# pure_battery.net
KiCad netlist of a schematic drawn in EAGLE
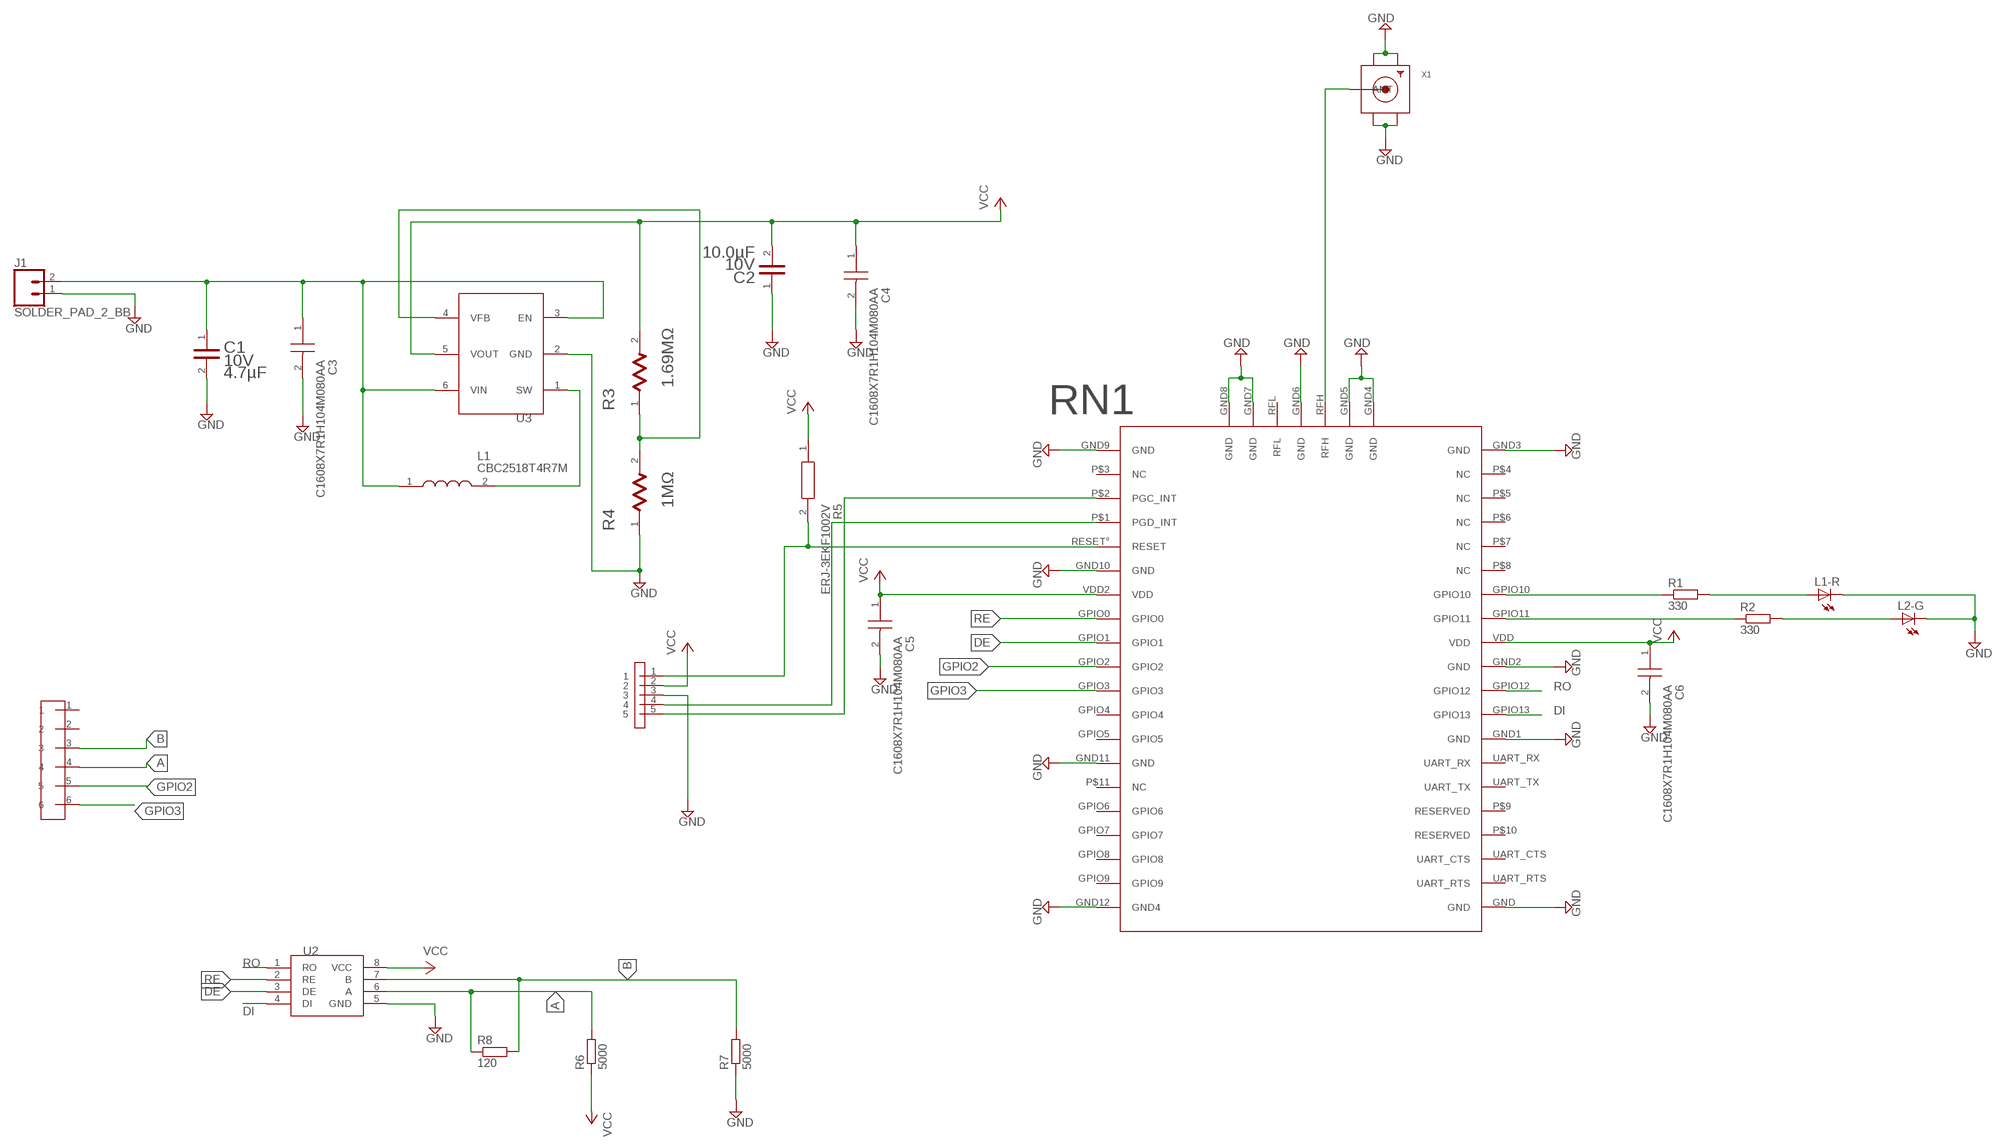
[diagram p0: schematic, sheet 1]

(export (version "E")
  (design (tool "Eeschema 10.0.6"))
  (components
    (comp (ref "C1")
      (value "KEMET_C0603C475K8PACTUKEMET_C0603C475K8PACTU_0_0")
      (footprint "eagle-import:KEMET_C0603C475K8PACTU_0")
      (fields
        (field (name "DIGIKEY_PART_NUMBER") "399-5503-1-ND")
        (field (name "MF") "Kemet")
        (field (name "MOUSER_PART_NUMBER") "80-C0603C475K8P")
      )
      (libsource (lib "eagle-import") (part "KEMET_C0603C475K8PACTUKEMET_C0603C475K8PACTU_0_0"))
    )
    (comp (ref "C2")
      (value "TDK_C1608X5R1A106M080ACTDK_C1608X5R1A106M080AC_0_0")
      (footprint "eagle-import:TDK_C1608X5R1A106M080AC_0")
      (fields
        (field (name "DIGIKEY_PART_NUMBER") "445-6853-1-ND")
        (field (name "MF") "TDK")
        (field (name "MOUSER_PART_NUMBER") "810-C1608X5R1A106M")
      )
      (libsource (lib "eagle-import") (part "TDK_C1608X5R1A106M080ACTDK_C1608X5R1A106M080AC_0_0"))
    )
    (comp (ref "C3")
      (value "C1608X7R1H104M080AA")
      (footprint "eagle-import:CAPC1608X80N")
      (fields (field (name "MOUSER_PART_NUMBER") "810-C1608X7R1H104M"))
      (libsource (lib "eagle-import") (part "C1608X7R1H104M080AA"))
    )
    (comp (ref "C4")
      (value "C1608X7R1H104M080AA")
      (footprint "eagle-import:CAPC1608X80N")
      (fields (field (name "MOUSER_PART_NUMBER") "810-C1608X7R1H104M"))
      (libsource (lib "eagle-import") (part "C1608X7R1H104M080AA"))
    )
    (comp (ref "C5")
      (value "C1608X7R1H104M080AA")
      (footprint "eagle-import:CAPC1608X80N")
      (fields (field (name "MOUSER_PART_NUMBER") "810-C1608X7R1H104M"))
      (libsource (lib "eagle-import") (part "C1608X7R1H104M080AA"))
    )
    (comp (ref "C6")
      (value "C1608X7R1H104M080AA")
      (footprint "eagle-import:CAPC1608X80N")
      (fields (field (name "MOUSER_PART_NUMBER") "810-C1608X7R1H104M"))
      (libsource (lib "eagle-import") (part "C1608X7R1H104M080AA"))
    )
    (comp (ref "J1")
      (value "SOLDER_PAD_2_BB")
      (footprint "eagle-import:SOLDER_PAD_2")
      (libsource (lib "eagle-import") (part "SOLDER_PAD_2_BB"))
    )
    (comp (ref "L1")
      (value "CBC2518T4R7M")
      (footprint "eagle-import:INDC2518X200N")
      (fields (field (name "MOUSER_PART_NUMBER") "963-CBC2518T4R7M"))
      (libsource (lib "eagle-import") (part "CBC2518T4R7M"))
    )
    (comp (ref "L1-R")
      (value "LEDCHIP-LED0603")
      (footprint "eagle-import:CHIP-LED0603")
      (libsource (lib "eagle-import") (part "LEDCHIP-LED0603"))
    )
    (comp (ref "L2-G")
      (value "LEDCHIP-LED0603")
      (footprint "eagle-import:CHIP-LED0603")
      (libsource (lib "eagle-import") (part "LEDCHIP-LED0603"))
    )
    (comp (ref "R1")
      (value "330")
      (footprint "eagle-import:R0603")
      (libsource (lib "eagle-import") (part "R-EU_R0603"))
    )
    (comp (ref "R2")
      (value "330")
      (footprint "eagle-import:R0603")
      (libsource (lib "eagle-import") (part "R-EU_R0603"))
    )
    (comp (ref "R3")
      (value "VISHAY_CRCW06031M69FKEAVISHAY_CRCW06031M69FKEA_0_1")
      (footprint "eagle-import:VISHAY_CRCW06031M69FKEA_1")
      (fields
        (field (name "APPROVED_ALTERNATE_PART_NUMBER") "541-1.00HHCT-ND")
        (field (name "DIGIKEY_PART_NUMBER") "541-1.69MHTR-ND")
        (field (name "MF") "Vishay")
      )
      (libsource (lib "eagle-import") (part "VISHAY_CRCW06031M69FKEAVISHAY_CRCW06031M69FKEA_0_1"))
    )
    (comp (ref "R4")
      (value "STACKPOLE_RMCF0603FT1M00STACKPOLE_RMCF0603FT1M00_0_1")
      (footprint "eagle-import:STACKPOLE_RMCF0603FT1M00_1")
      (fields
        (field (name "APPROVED_ALTERNATE_PART_NUMBER") "541-1.00HHCT-ND")
        (field (name "DIGIKEY_PART_NUMBER") "RMCF0603FT1M00-ND")
        (field (name "MF") "Stackpole")
      )
      (libsource (lib "eagle-import") (part "STACKPOLE_RMCF0603FT1M00STACKPOLE_RMCF0603FT1M00_0_1"))
    )
    (comp (ref "R5")
      (value "ERJ-3EKF1002V")
      (footprint "eagle-import:RESC1608X55N")
      (fields (field (name "MOUSER_PART_NUMBER") "667-ERJ-3EKF1002V"))
      (libsource (lib "eagle-import") (part "ERJ-3EKF1002V"))
    )
    (comp (ref "R6")
      (value "5000")
      (footprint "eagle-import:R0805")
      (libsource (lib "eagle-import") (part "R-EU_R0805"))
    )
    (comp (ref "R7")
      (value "5000")
      (footprint "eagle-import:R0805")
      (libsource (lib "eagle-import") (part "R-EU_R0805"))
    )
    (comp (ref "R8")
      (value "120")
      (footprint "eagle-import:R0805")
      (libsource (lib "eagle-import") (part "R-EU_R0805"))
    )
    (comp (ref "RN1")
      (value "NEW_RN2483")
      (footprint "eagle-import:NEW_RN2483")
      (libsource (lib "eagle-import") (part "NEW_RN2483"))
    )
    (comp (ref "U$1")
      (value "CONNECTOR6_V2")
      (footprint "eagle-import:CONNECTOR6_V2")
      (libsource (lib "eagle-import") (part "CONNECTOR6_V2"))
    )
    (comp (ref "U$2")
      (value "ICSP_V2")
      (footprint "eagle-import:ICSP_V2")
      (libsource (lib "eagle-import") (part "ICSP_V2"))
    )
    (comp (ref "U2")
      (value "AMD3485E")
      (footprint "eagle-import:AMD3485E")
      (libsource (lib "eagle-import") (part "AMD3485E"))
    )
    (comp (ref "U3")
      (value "MCP16252")
      (footprint "eagle-import:MCP16252")
      (libsource (lib "eagle-import") (part "MCP16252"))
    )
    (comp (ref "X1")
      (value "SMACONNECTOR_EDGE")
      (footprint "eagle-import:SMA_EDGELAUNCH")
      (libsource (lib "eagle-import") (part "SMACONNECTOR_EDGE"))
    )
  )
  (nets
    (net (code "1") (name "/DI") (class "Default")
      (node (ref "RN1") (pin "GPIO13") (pinfunction "GPIO13_GPIO13") (pintype "bidirectional"))
      (node (ref "U2") (pin "4") (pinfunction "DI_4") (pintype "bidirectional"))
    )
    (net (code "2") (name "/RO") (class "Default")
      (node (ref "RN1") (pin "GPIO12") (pinfunction "GPIO12_GPIO12") (pintype "bidirectional"))
      (node (ref "U2") (pin "1") (pinfunction "RO_1") (pintype "bidirectional"))
    )
    (net (code "3") (name "A") (class "Default")
      (node (ref "R6") (pin "2") (pinfunction "2_2") (pintype "passive"))
      (node (ref "R8") (pin "1") (pinfunction "1_1") (pintype "passive"))
      (node (ref "U$1") (pin "4") (pinfunction "4_4") (pintype "bidirectional"))
      (node (ref "U2") (pin "6") (pinfunction "A_6") (pintype "bidirectional"))
    )
    (net (code "4") (name "B") (class "Default")
      (node (ref "R7") (pin "2") (pinfunction "2_2") (pintype "passive"))
      (node (ref "R8") (pin "2") (pinfunction "2_2") (pintype "passive"))
      (node (ref "U$1") (pin "3") (pinfunction "3_3") (pintype "bidirectional"))
      (node (ref "U2") (pin "7") (pinfunction "B_7") (pintype "bidirectional"))
    )
    (net (code "5") (name "DE") (class "Default")
      (node (ref "RN1") (pin "GPIO1") (pinfunction "GPIO1_GPIO1") (pintype "bidirectional"))
      (node (ref "U2") (pin "3") (pinfunction "DE_3") (pintype "bidirectional"))
    )
    (net (code "6") (name "GND") (class "Default")
      (node (ref "C1") (pin "2") (pinfunction "2_2") (pintype "bidirectional"))
      (node (ref "C2") (pin "1") (pinfunction "1_1") (pintype "bidirectional"))
      (node (ref "C3") (pin "2") (pinfunction "2_2") (pintype "bidirectional"))
      (node (ref "C4") (pin "2") (pinfunction "2_2") (pintype "bidirectional"))
      (node (ref "C5") (pin "2") (pinfunction "2_2") (pintype "bidirectional"))
      (node (ref "C6") (pin "2") (pinfunction "2_2") (pintype "bidirectional"))
      (node (ref "J1") (pin "1") (pinfunction "1_1") (pintype "passive"))
      (node (ref "L1-R") (pin "C") (pinfunction "C_C") (pintype "passive"))
      (node (ref "L2-G") (pin "C") (pinfunction "C_C") (pintype "passive"))
      (node (ref "R4") (pin "1") (pinfunction "1_1") (pintype "passive"))
      (node (ref "R7") (pin "1") (pinfunction "1_1") (pintype "passive"))
      (node (ref "RN1") (pin "GND") (pinfunction "GND_GND") (pintype "bidirectional"))
      (node (ref "RN1") (pin "GND1") (pinfunction "GND_GND1") (pintype "bidirectional"))
      (node (ref "RN1") (pin "GND10") (pinfunction "GND_GND10") (pintype "bidirectional"))
      (node (ref "RN1") (pin "GND11") (pinfunction "GND_GND11") (pintype "bidirectional"))
      (node (ref "RN1") (pin "GND12") (pinfunction "GND4_GND12") (pintype "bidirectional"))
      (node (ref "RN1") (pin "GND2") (pinfunction "GND_GND2") (pintype "bidirectional"))
      (node (ref "RN1") (pin "GND3") (pinfunction "GND_GND3") (pintype "bidirectional"))
      (node (ref "RN1") (pin "GND4") (pinfunction "GND_GND4") (pintype "bidirectional"))
      (node (ref "RN1") (pin "GND5") (pinfunction "GND_GND5") (pintype "bidirectional"))
      (node (ref "RN1") (pin "GND6") (pinfunction "GND_GND6") (pintype "bidirectional"))
      (node (ref "RN1") (pin "GND7") (pinfunction "GND_GND7") (pintype "bidirectional"))
      (node (ref "RN1") (pin "GND8") (pinfunction "GND_GND8") (pintype "bidirectional"))
      (node (ref "RN1") (pin "GND9") (pinfunction "GND_GND9") (pintype "bidirectional"))
      (node (ref "U$2") (pin "3") (pinfunction "3_3") (pintype "bidirectional"))
      (node (ref "U2") (pin "5") (pinfunction "GND_5") (pintype "bidirectional"))
      (node (ref "U3") (pin "2") (pinfunction "GND_2") (pintype "bidirectional"))
      (node (ref "X1") (pin "GND@1") (pinfunction "GND4_GND@1") (pintype "power_in"))
      (node (ref "X1") (pin "GND@2") (pinfunction "GND3_GND@2") (pintype "power_in"))
      (node (ref "X1") (pin "GND@3") (pinfunction "GND2_GND@3") (pintype "power_in"))
      (node (ref "X1") (pin "GND@4") (pinfunction "GND1_GND@4") (pintype "power_in"))
    )
    (net (code "7") (name "GPIO2") (class "Default")
      (node (ref "RN1") (pin "GPIO2") (pinfunction "GPIO2_GPIO2") (pintype "bidirectional"))
      (node (ref "U$1") (pin "5") (pinfunction "5_5") (pintype "bidirectional"))
    )
    (net (code "8") (name "GPIO3") (class "Default")
      (node (ref "RN1") (pin "GPIO3") (pinfunction "GPIO3_GPIO3") (pintype "bidirectional"))
      (node (ref "U$1") (pin "6") (pinfunction "6_6") (pintype "bidirectional"))
    )
    (net (code "9") (name "Net-(L1-R-PadA)") (class "Default")
      (node (ref "L1-R") (pin "A") (pinfunction "A_A") (pintype "passive"))
      (node (ref "R1") (pin "2") (pinfunction "2_2") (pintype "passive"))
    )
    (net (code "10") (name "Net-(L2-G-PadA)") (class "Default")
      (node (ref "L2-G") (pin "A") (pinfunction "A_A") (pintype "passive"))
      (node (ref "R2") (pin "2") (pinfunction "2_2") (pintype "passive"))
    )
    (net (code "11") (name "Net-(R1-Pad1)") (class "Default")
      (node (ref "R1") (pin "1") (pinfunction "1_1") (pintype "passive"))
      (node (ref "RN1") (pin "GPIO10") (pinfunction "GPIO10_GPIO10") (pintype "bidirectional"))
    )
    (net (code "12") (name "Net-(R2-Pad1)") (class "Default")
      (node (ref "R2") (pin "1") (pinfunction "1_1") (pintype "passive"))
      (node (ref "RN1") (pin "GPIO11") (pinfunction "GPIO11_GPIO11") (pintype "bidirectional"))
    )
    (net (code "13") (name "Net-(RN1-PGC_INT)") (class "Default")
      (node (ref "RN1") (pin "P$2") (pinfunction "PGC_INT_P$2") (pintype "bidirectional"))
      (node (ref "U$2") (pin "5") (pinfunction "5_5") (pintype "bidirectional"))
    )
    (net (code "14") (name "Net-(RN1-PGD_INT)") (class "Default")
      (node (ref "RN1") (pin "P$1") (pinfunction "PGD_INT_P$1") (pintype "bidirectional"))
      (node (ref "U$2") (pin "4") (pinfunction "4_4") (pintype "bidirectional"))
    )
    (net (code "15") (name "Net-(RN1-RESET)") (class "Default")
      (node (ref "R5") (pin "2") (pinfunction "2_2") (pintype "bidirectional"))
      (node (ref "RN1") (pin "RESET°") (pinfunction "RESET_RESET°") (pintype "bidirectional"))
      (node (ref "U$2") (pin "1") (pinfunction "1_1") (pintype "bidirectional"))
    )
    (net (code "16") (name "Net-(U3-EN)") (class "Default")
      (node (ref "C1") (pin "1") (pinfunction "1_1") (pintype "bidirectional"))
      (node (ref "C3") (pin "1") (pinfunction "1_1") (pintype "bidirectional"))
      (node (ref "J1") (pin "2") (pinfunction "2_2") (pintype "passive"))
      (node (ref "L1") (pin "1") (pinfunction "1_1") (pintype "bidirectional"))
      (node (ref "U3") (pin "3") (pinfunction "EN_3") (pintype "bidirectional"))
      (node (ref "U3") (pin "6") (pinfunction "VIN_6") (pintype "bidirectional"))
    )
    (net (code "17") (name "Net-(U3-SW)") (class "Default")
      (node (ref "L1") (pin "2") (pinfunction "2_2") (pintype "bidirectional"))
      (node (ref "U3") (pin "1") (pinfunction "SW_1") (pintype "bidirectional"))
    )
    (net (code "18") (name "Net-(U3-VFB)") (class "Default")
      (node (ref "R3") (pin "1") (pinfunction "1_1") (pintype "passive"))
      (node (ref "R4") (pin "2") (pinfunction "2_2") (pintype "passive"))
      (node (ref "U3") (pin "4") (pinfunction "VFB_4") (pintype "bidirectional"))
    )
    (net (code "19") (name "Net-(X1-ANT)") (class "Default")
      (node (ref "RN1") (pin "RFH") (pinfunction "RFH_RFH") (pintype "bidirectional"))
      (node (ref "X1") (pin "P") (pinfunction "ANT_P") (pintype "bidirectional"))
    )
    (net (code "20") (name "RE") (class "Default")
      (node (ref "RN1") (pin "GPIO0") (pinfunction "GPIO0_GPIO0") (pintype "bidirectional"))
      (node (ref "U2") (pin "2") (pinfunction "RE_2") (pintype "bidirectional"))
    )
    (net (code "21") (name "VCC") (class "Default")
      (node (ref "C2") (pin "2") (pinfunction "2_2") (pintype "bidirectional"))
      (node (ref "C4") (pin "1") (pinfunction "1_1") (pintype "bidirectional"))
      (node (ref "C5") (pin "1") (pinfunction "1_1") (pintype "bidirectional"))
      (node (ref "C6") (pin "1") (pinfunction "1_1") (pintype "bidirectional"))
      (node (ref "R3") (pin "2") (pinfunction "2_2") (pintype "passive"))
      (node (ref "R5") (pin "1") (pinfunction "1_1") (pintype "bidirectional"))
      (node (ref "R6") (pin "1") (pinfunction "1_1") (pintype "passive"))
      (node (ref "RN1") (pin "VDD") (pinfunction "VDD_VDD") (pintype "bidirectional"))
      (node (ref "RN1") (pin "VDD2") (pinfunction "VDD_VDD2") (pintype "bidirectional"))
      (node (ref "U$2") (pin "2") (pinfunction "2_2") (pintype "bidirectional"))
      (node (ref "U2") (pin "8") (pinfunction "VCC_8") (pintype "bidirectional"))
      (node (ref "U3") (pin "5") (pinfunction "VOUT_5") (pintype "bidirectional"))
    )
    (net (code "22") (name "unconnected-(RN1-NC-PadP$3)") (class "Default")
      (node (ref "RN1") (pin "P$3") (pinfunction "NC_P$3") (pintype "bidirectional"))
    )
    (net (code "23") (name "unconnected-(RN1-NC-PadP$4)") (class "Default")
      (node (ref "RN1") (pin "P$4") (pinfunction "NC_P$4") (pintype "bidirectional"))
    )
    (net (code "24") (name "unconnected-(RN1-NC-PadP$5)") (class "Default")
      (node (ref "RN1") (pin "P$5") (pinfunction "NC_P$5") (pintype "bidirectional"))
    )
    (net (code "25") (name "unconnected-(RN1-NC-PadP$6)") (class "Default")
      (node (ref "RN1") (pin "P$6") (pinfunction "NC_P$6") (pintype "bidirectional"))
    )
    (net (code "26") (name "unconnected-(RN1-NC-PadP$7)") (class "Default")
      (node (ref "RN1") (pin "P$7") (pinfunction "NC_P$7") (pintype "bidirectional"))
    )
    (net (code "27") (name "unconnected-(RN1-NC-PadP$8)") (class "Default")
      (node (ref "RN1") (pin "P$8") (pinfunction "NC_P$8") (pintype "bidirectional"))
    )
    (net (code "28") (name "unconnected-(RN1-NC-PadP$11)") (class "Default")
      (node (ref "RN1") (pin "P$11") (pinfunction "NC_P$11") (pintype "bidirectional"))
    )
    (net (code "29") (name "unconnected-(RN1-PadGPIO4)") (class "Default")
      (node (ref "RN1") (pin "GPIO4") (pinfunction "GPIO4_GPIO4") (pintype "bidirectional"))
    )
    (net (code "30") (name "unconnected-(RN1-PadGPIO5)") (class "Default")
      (node (ref "RN1") (pin "GPIO5") (pinfunction "GPIO5_GPIO5") (pintype "bidirectional"))
    )
    (net (code "31") (name "unconnected-(RN1-PadGPIO6)") (class "Default")
      (node (ref "RN1") (pin "GPIO6") (pinfunction "GPIO6_GPIO6") (pintype "bidirectional"))
    )
    (net (code "32") (name "unconnected-(RN1-PadGPIO7)") (class "Default")
      (node (ref "RN1") (pin "GPIO7") (pinfunction "GPIO7_GPIO7") (pintype "bidirectional"))
    )
    (net (code "33") (name "unconnected-(RN1-PadGPIO8)") (class "Default")
      (node (ref "RN1") (pin "GPIO8") (pinfunction "GPIO8_GPIO8") (pintype "bidirectional"))
    )
    (net (code "34") (name "unconnected-(RN1-PadGPIO9)") (class "Default")
      (node (ref "RN1") (pin "GPIO9") (pinfunction "GPIO9_GPIO9") (pintype "bidirectional"))
    )
    (net (code "35") (name "unconnected-(RN1-PadRFL)") (class "Default")
      (node (ref "RN1") (pin "RFL") (pinfunction "RFL_RFL") (pintype "bidirectional"))
    )
    (net (code "36") (name "unconnected-(RN1-PadUART_CTS)") (class "Default")
      (node (ref "RN1") (pin "UART_CTS") (pinfunction "UART_CTS_UART_CTS") (pintype "bidirectional"))
    )
    (net (code "37") (name "unconnected-(RN1-PadUART_RTS)") (class "Default")
      (node (ref "RN1") (pin "UART_RTS") (pinfunction "UART_RTS_UART_RTS") (pintype "bidirectional"))
    )
    (net (code "38") (name "unconnected-(RN1-PadUART_RX)") (class "Default")
      (node (ref "RN1") (pin "UART_RX") (pinfunction "UART_RX_UART_RX") (pintype "bidirectional"))
    )
    (net (code "39") (name "unconnected-(RN1-PadUART_TX)") (class "Default")
      (node (ref "RN1") (pin "UART_TX") (pinfunction "UART_TX_UART_TX") (pintype "bidirectional"))
    )
    (net (code "40") (name "unconnected-(RN1-RESERVED-PadP$9)") (class "Default")
      (node (ref "RN1") (pin "P$9") (pinfunction "RESERVED_P$9") (pintype "bidirectional"))
    )
    (net (code "41") (name "unconnected-(RN1-RESERVED-PadP$10)") (class "Default")
      (node (ref "RN1") (pin "P$10") (pinfunction "RESERVED_P$10") (pintype "bidirectional"))
    )
    (net (code "42") (name "unconnected-(U$1-Pad1)") (class "Default")
      (node (ref "U$1") (pin "1") (pinfunction "1_1") (pintype "bidirectional"))
    )
    (net (code "43") (name "unconnected-(U$1-Pad2)") (class "Default")
      (node (ref "U$1") (pin "2") (pinfunction "2_2") (pintype "bidirectional"))
    )
  )
)
